# Comms.net
KiCad netlist of a schematic drawn in Altium Designer
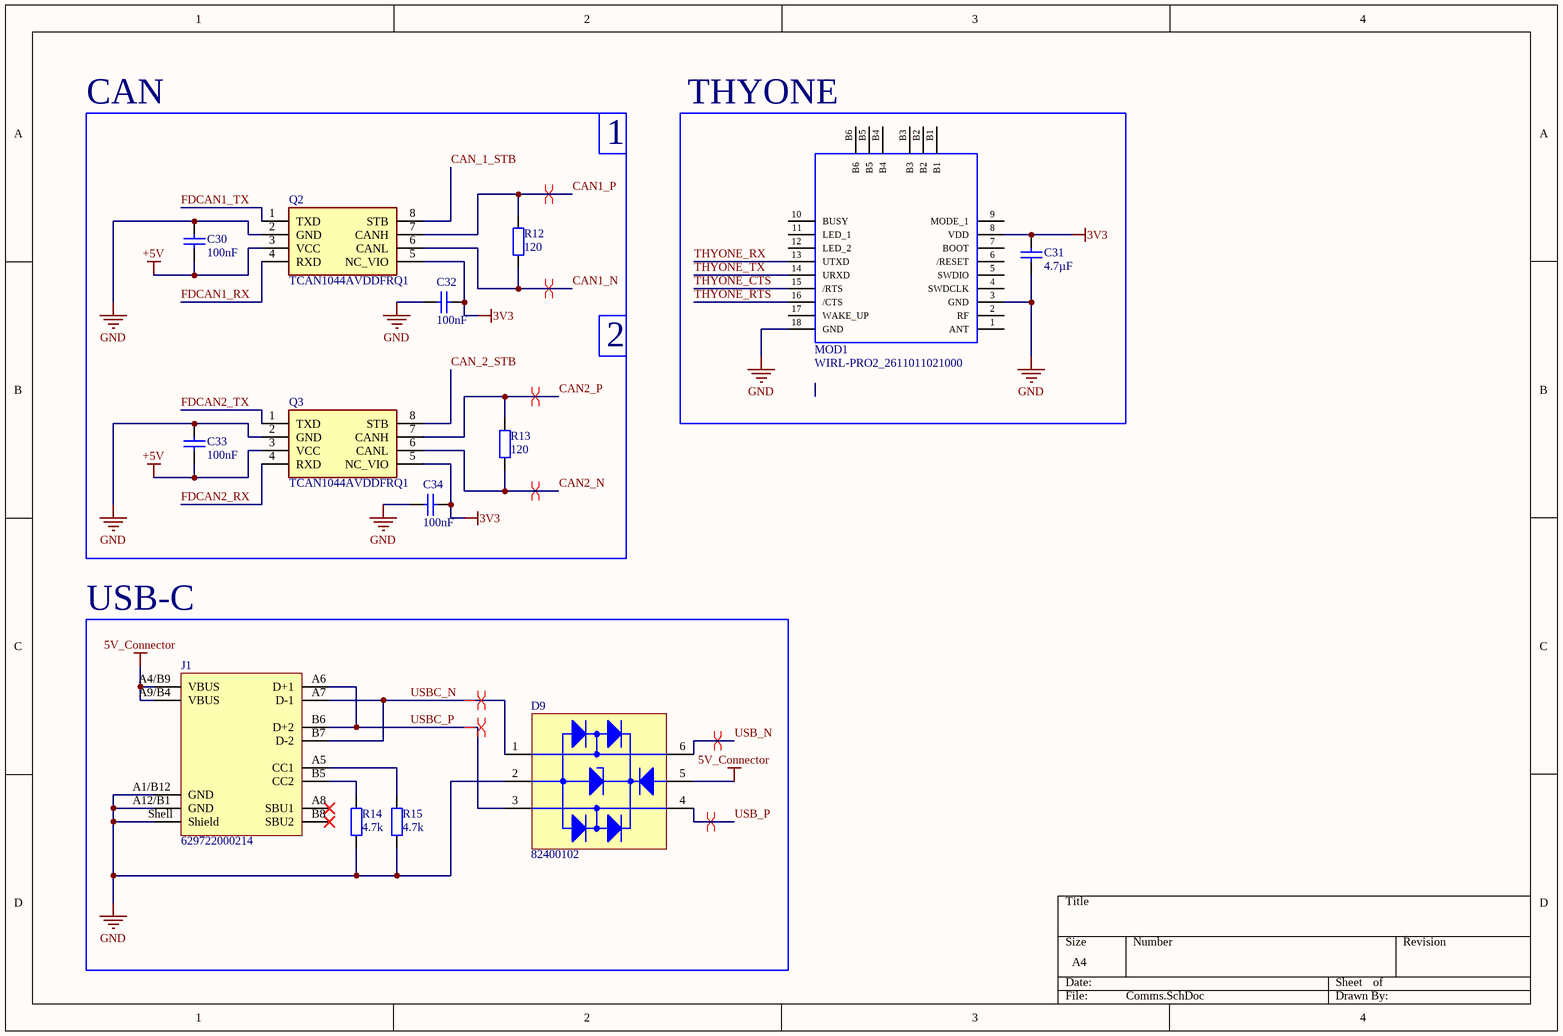
[diagram p0: Comms.SchDoc]

(export (version "E")
  (design (tool "Eeschema 10.0.6"))
  (components
    (comp (ref "C30")
      (value "100nF")
      (footprint "WCAP-CSGP_0603_L1.6W0.8H0.8_Reflow")
      (description "WCAP-CSGP Multilayer Ceramic Chip Capacitor, General Purpose, size 0603, X7R, 100nF, 25VDC")
      (fields
        (field (name "MANUFACTURER") "Wurth Elektronik")
        (field (name "MANUFACTURER PART NUMBER") "885012206071")
      )
      (libsource (lib "LEEM UPM") (part "885012209047R"))
    )
    (comp (ref "C31")
      (value "4.7µF")
      (footprint "WCAP-CSGP_0603_L1.6W0.8H0.8_Reflow")
      (description "WCAP-CSGP Multilayer Ceramic Chip Capacitor, General Purpose, size 0603, X5R, 4.7uF, 10VDC")
      (fields
        (field (name "MANUFACTURER PART NUMBER") "885012106012")
        (field (name "MANUFACTURER") "Wurth Elektronik")
      )
      (libsource (lib "LEEM UPM") (part "885012209047R"))
    )
    (comp (ref "C32")
      (value "100nF")
      (footprint "WCAP-CSGP_0603_L1.6W0.8H0.8_Reflow")
      (description "WCAP-CSGP Multilayer Ceramic Chip Capacitor, General Purpose, size 0603, X7R, 100nF, 25VDC")
      (fields
        (field (name "MANUFACTURER") "Wurth Elektronik")
        (field (name "MANUFACTURER PART NUMBER") "885012206071")
      )
      (libsource (lib "LEEM UPM") (part "885012209047R"))
    )
    (comp (ref "C33")
      (value "100nF")
      (footprint "WCAP-CSGP_0603_L1.6W0.8H0.8_Reflow")
      (description "WCAP-CSGP Multilayer Ceramic Chip Capacitor, General Purpose, size 0603, X7R, 100nF, 25VDC")
      (fields
        (field (name "MANUFACTURER") "Wurth Elektronik")
        (field (name "MANUFACTURER PART NUMBER") "885012206071")
      )
      (libsource (lib "LEEM UPM") (part "885012209047R"))
    )
    (comp (ref "C34")
      (value "100nF")
      (footprint "WCAP-CSGP_0603_L1.6W0.8H0.8_Reflow")
      (description "WCAP-CSGP Multilayer Ceramic Chip Capacitor, General Purpose, size 0603, X7R, 100nF, 25VDC")
      (fields
        (field (name "MANUFACTURER") "Wurth Elektronik")
        (field (name "MANUFACTURER PART NUMBER") "885012206071")
      )
      (libsource (lib "LEEM UPM") (part "885012209047R"))
    )
    (comp (ref "D9")
      (value "82400102")
      (footprint "WE-TVS_SOT23-6L")
      (description "WE-TVS TVS Diode – High Speed Series, SOT23-6L, 2+1 Channel, 5V, 2pF")
      (fields (field (name "MANUFACTURER") "Wurth Elektronik"))
      (libsource (lib "LEEM UPM") (part "82400152"))
    )
    (comp (ref "J1")
      (value "629722000214")
      (footprint "629722000214")
      (description "WR-COM USB 2.0 Type C Receptacle Horizontal SMT")
      (fields (field (name "MANUFACTURER") "Wurth Elektronik"))
      (libsource (lib "LEEM UPM") (part "629722000214"))
    )
    (comp (ref "MOD1")
      (value "WIRL-PRO2_2611011021000")
      (footprint "WE-FP-4+")
      (description "Thyone-I - Radio Modules 2.4 GHz")
      (fields (field (name "PART NUMBER") "2611011021000") (field (name "PUBLISHER") "Wurth Elektronik"))
      (libsource (lib "LEEM UPM") (part "WIRL-PRO2_2611011021000"))
    )
    (comp (ref "Q2")
      (value "TCAN1044AVDDFRQ1")
      (footprint "FP-DDF0008A-MFG")
      (description "Enhanced automotive CAN transceiver with standby 8-SOT-23-THIN -40 to 150")
      (libsource (lib "LEEM UPM") (part "TCAN1044A"))
    )
    (comp (ref "Q3")
      (value "TCAN1044AVDDFRQ1")
      (footprint "FP-DDF0008A-MFG")
      (description "Enhanced automotive CAN transceiver with standby 8-SOT-23-THIN -40 to 150")
      (libsource (lib "LEEM UPM") (part "TCAN1044A"))
    )
    (comp (ref "R12")
      (value "120")
      (footprint "RCS0805120RFKEA-Footprint-1")
      (fields (field (name "POWER") "500mW") (field (name "Comment") "RCS0805120RFKEA"))
      (libsource (lib "LEEM UPM") (part "RCS0805120"))
    )
    (comp (ref "R13")
      (value "120")
      (footprint "RCS0805120RFKEA-Footprint-1")
      (fields (field (name "POWER") "500mW") (field (name "Comment") "RCS0805120RFKEA"))
      (libsource (lib "LEEM UPM") (part "RCS0805120"))
    )
    (comp (ref "R14")
      (value "4.7k")
      (footprint "WRIS-RSKS_0603_Reflow")
      (description "WRIS-RSKS Thick Film Resistor, size 0603, 4700Ohm, 100mW")
      (fields
        (field (name "MANUFACTURER PART NUMBER") "560112116006")
        (field (name "MANUFACTURER") "Wurth Elektronik")
      )
      (libsource (lib "LEEM UPM") (part "560112140010"))
    )
    (comp (ref "R15")
      (value "4.7k")
      (footprint "WRIS-RSKS_0603_Reflow")
      (description "WRIS-RSKS Thick Film Resistor, size 0603, 4700Ohm, 100mW")
      (fields
        (field (name "MANUFACTURER PART NUMBER") "560112116006")
        (field (name "MANUFACTURER") "Wurth Elektronik")
      )
      (libsource (lib "LEEM UPM") (part "560112140010"))
    )
  )
  (nets
    (net (code "1") (name "+5V") (class "Default")
      (node (ref "C30") (pin "1") (pinfunction "1_1") (pintype "passive"))
      (node (ref "C33") (pin "1") (pinfunction "1_1") (pintype "passive"))
      (node (ref "Q2") (pin "3") (pinfunction "VCC_3") (pintype "passive"))
      (node (ref "Q3") (pin "3") (pinfunction "VCC_3") (pintype "passive"))
    )
    (net (code "2") (name "/CAN1_N") (class "Default")
      (node (ref "Q2") (pin "6") (pinfunction "CANL_6") (pintype "passive"))
      (node (ref "R12") (pin "1") (pinfunction "1_1") (pintype "passive"))
    )
    (net (code "3") (name "/CAN1_P") (class "Default")
      (node (ref "Q2") (pin "7") (pinfunction "CANH_7") (pintype "passive"))
      (node (ref "R12") (pin "2") (pinfunction "2_2") (pintype "passive"))
    )
    (net (code "4") (name "/CAN2_N") (class "Default")
      (node (ref "Q3") (pin "6") (pinfunction "CANL_6") (pintype "passive"))
      (node (ref "R13") (pin "1") (pinfunction "1_1") (pintype "passive"))
    )
    (net (code "5") (name "/CAN2_P") (class "Default")
      (node (ref "Q3") (pin "7") (pinfunction "CANH_7") (pintype "passive"))
      (node (ref "R13") (pin "2") (pinfunction "2_2") (pintype "passive"))
    )
    (net (code "6") (name "/CAN_1_STB") (class "Default")
      (node (ref "Q2") (pin "8") (pinfunction "STB_8") (pintype "passive"))
    )
    (net (code "7") (name "/CAN_2_STB") (class "Default")
      (node (ref "Q3") (pin "8") (pinfunction "STB_8") (pintype "passive"))
    )
    (net (code "8") (name "/FDCAN1_RX") (class "Default")
      (node (ref "Q2") (pin "4") (pinfunction "RXD_4") (pintype "passive"))
    )
    (net (code "9") (name "/FDCAN1_TX") (class "Default")
      (node (ref "Q2") (pin "1") (pinfunction "TXD_1") (pintype "passive"))
    )
    (net (code "10") (name "/FDCAN2_RX") (class "Default")
      (node (ref "Q3") (pin "4") (pinfunction "RXD_4") (pintype "passive"))
    )
    (net (code "11") (name "/FDCAN2_TX") (class "Default")
      (node (ref "Q3") (pin "1") (pinfunction "TXD_1") (pintype "passive"))
    )
    (net (code "12") (name "/THYONE_CTS") (class "Default")
      (node (ref "MOD1") (pin "15") (pinfunction "/RTS_15") (pintype "passive"))
    )
    (net (code "13") (name "/THYONE_RTS") (class "Default")
      (node (ref "MOD1") (pin "16") (pinfunction "/CTS_16") (pintype "passive"))
    )
    (net (code "14") (name "/THYONE_RX") (class "Default")
      (node (ref "MOD1") (pin "13") (pinfunction "UTXD_13") (pintype "passive"))
    )
    (net (code "15") (name "/THYONE_TX") (class "Default")
      (node (ref "MOD1") (pin "14") (pinfunction "URXD_14") (pintype "passive"))
    )
    (net (code "16") (name "/USBC_N") (class "Default")
      (node (ref "D9") (pin "1") (pinfunction "I/O_1_1") (pintype "passive"))
      (node (ref "J1") (pin "A7") (pinfunction "D-1_A7") (pintype "passive"))
      (node (ref "J1") (pin "B7") (pinfunction "D-2_B7") (pintype "passive"))
    )
    (net (code "17") (name "/USBC_P") (class "Default")
      (node (ref "D9") (pin "3") (pinfunction "I/O_2_3") (pintype "passive"))
      (node (ref "J1") (pin "A6") (pinfunction "D+1_A6") (pintype "passive"))
      (node (ref "J1") (pin "B6") (pinfunction "D+2_B6") (pintype "passive"))
    )
    (net (code "18") (name "/USB_N") (class "Default")
      (node (ref "D9") (pin "6") (pinfunction "I/O_1_6") (pintype "passive"))
    )
    (net (code "19") (name "/USB_P") (class "Default")
      (node (ref "D9") (pin "4") (pinfunction "I/O_2_4") (pintype "passive"))
    )
    (net (code "20") (name "3V3") (class "Default")
      (node (ref "C31") (pin "1") (pinfunction "1_1") (pintype "passive"))
      (node (ref "C32") (pin "1") (pinfunction "1_1") (pintype "passive"))
      (node (ref "C34") (pin "1") (pinfunction "1_1") (pintype "passive"))
      (node (ref "MOD1") (pin "8") (pinfunction "VDD_8") (pintype "passive"))
      (node (ref "Q2") (pin "5") (pinfunction "NC_VIO_5") (pintype "passive"))
      (node (ref "Q3") (pin "5") (pinfunction "NC_VIO_5") (pintype "passive"))
    )
    (net (code "21") (name "5V_Connector") (class "Default")
      (node (ref "D9") (pin "5") (pinfunction "VDD_5") (pintype "passive"))
      (node (ref "J1") (pin "A4/B9") (pinfunction "VBUS_A4/B9") (pintype "passive"))
      (node (ref "J1") (pin "A9/B4") (pinfunction "VBUS_A9/B4") (pintype "passive"))
    )
    (net (code "22") (name "GND") (class "Default")
      (node (ref "C30") (pin "2") (pinfunction "2_2") (pintype "passive"))
      (node (ref "C31") (pin "2") (pinfunction "2_2") (pintype "passive"))
      (node (ref "C32") (pin "2") (pinfunction "2_2") (pintype "passive"))
      (node (ref "C33") (pin "2") (pinfunction "2_2") (pintype "passive"))
      (node (ref "C34") (pin "2") (pinfunction "2_2") (pintype "passive"))
      (node (ref "D9") (pin "2") (pinfunction "GND_2") (pintype "passive"))
      (node (ref "J1") (pin "A1/B12") (pinfunction "GND_A1/B12") (pintype "passive"))
      (node (ref "J1") (pin "A12/B1") (pinfunction "GND_A12/B1") (pintype "passive"))
      (node (ref "J1") (pin "Shell") (pinfunction "Shield_Shell") (pintype "passive"))
      (node (ref "MOD1") (pin "18") (pinfunction "GND_18") (pintype "passive"))
      (node (ref "MOD1") (pin "3") (pinfunction "GND_3") (pintype "passive"))
      (node (ref "Q2") (pin "2") (pinfunction "GND_2") (pintype "passive"))
      (node (ref "Q3") (pin "2") (pinfunction "GND_2") (pintype "passive"))
      (node (ref "R14") (pin "2") (pinfunction "2_2") (pintype "passive"))
      (node (ref "R15") (pin "2") (pinfunction "2_2") (pintype "passive"))
    )
    (net (code "23") (name "Net-(J1-CC1)") (class "Default")
      (node (ref "J1") (pin "A5") (pinfunction "CC1_A5") (pintype "passive"))
      (node (ref "R15") (pin "1") (pinfunction "1_1") (pintype "passive"))
    )
    (net (code "24") (name "Net-(J1-CC2)") (class "Default")
      (node (ref "J1") (pin "B5") (pinfunction "CC2_B5") (pintype "passive"))
      (node (ref "R14") (pin "1") (pinfunction "1_1") (pintype "passive"))
    )
    (net (code "25") (name "unconnected-(J1-SBU1-PadA8)") (class "Default")
      (node (ref "J1") (pin "A8") (pinfunction "SBU1_A8") (pintype "passive+no_connect"))
    )
    (net (code "26") (name "unconnected-(J1-SBU2-PadB8)") (class "Default")
      (node (ref "J1") (pin "B8") (pinfunction "SBU2_B8") (pintype "passive+no_connect"))
    )
    (net (code "27") (name "unconnected-(MOD1-ANT-Pad1)") (class "Default")
      (node (ref "MOD1") (pin "1") (pinfunction "ANT_1") (pintype "passive"))
    )
    (net (code "28") (name "unconnected-(MOD1-BOOT-Pad7)") (class "Default")
      (node (ref "MOD1") (pin "7") (pinfunction "BOOT_7") (pintype "passive"))
    )
    (net (code "29") (name "unconnected-(MOD1-BUSY-Pad10)") (class "Default")
      (node (ref "MOD1") (pin "10") (pinfunction "BUSY_10") (pintype "passive"))
    )
    (net (code "30") (name "unconnected-(MOD1-LED_1-Pad11)") (class "Default")
      (node (ref "MOD1") (pin "11") (pinfunction "LED_1_11") (pintype "passive"))
    )
    (net (code "31") (name "unconnected-(MOD1-LED_2-Pad12)") (class "Default")
      (node (ref "MOD1") (pin "12") (pinfunction "LED_2_12") (pintype "passive"))
    )
    (net (code "32") (name "unconnected-(MOD1-MODE_1-Pad9)") (class "Default")
      (node (ref "MOD1") (pin "9") (pinfunction "MODE_1_9") (pintype "passive"))
    )
    (net (code "33") (name "unconnected-(MOD1-PadB1)") (class "Default")
      (node (ref "MOD1") (pin "B1") (pinfunction "B1_B1") (pintype "passive"))
    )
    (net (code "34") (name "unconnected-(MOD1-PadB2)") (class "Default")
      (node (ref "MOD1") (pin "B2") (pinfunction "B2_B2") (pintype "passive"))
    )
    (net (code "35") (name "unconnected-(MOD1-PadB3)") (class "Default")
      (node (ref "MOD1") (pin "B3") (pinfunction "B3_B3") (pintype "passive"))
    )
    (net (code "36") (name "unconnected-(MOD1-PadB4)") (class "Default")
      (node (ref "MOD1") (pin "B4") (pinfunction "B4_B4") (pintype "passive"))
    )
    (net (code "37") (name "unconnected-(MOD1-PadB5)") (class "Default")
      (node (ref "MOD1") (pin "B5") (pinfunction "B5_B5") (pintype "passive"))
    )
    (net (code "38") (name "unconnected-(MOD1-PadB6)") (class "Default")
      (node (ref "MOD1") (pin "B6") (pinfunction "B6_B6") (pintype "passive"))
    )
    (net (code "39") (name "unconnected-(MOD1-RF-Pad2)") (class "Default")
      (node (ref "MOD1") (pin "2") (pinfunction "RF_2") (pintype "passive"))
    )
    (net (code "40") (name "unconnected-(MOD1-SWDCLK-Pad4)") (class "Default")
      (node (ref "MOD1") (pin "4") (pinfunction "SWDCLK_4") (pintype "passive"))
    )
    (net (code "41") (name "unconnected-(MOD1-SWDIO-Pad5)") (class "Default")
      (node (ref "MOD1") (pin "5") (pinfunction "SWDIO_5") (pintype "passive"))
    )
    (net (code "42") (name "unconnected-(MOD1-WAKE_UP-Pad17)") (class "Default")
      (node (ref "MOD1") (pin "17") (pinfunction "WAKE_UP_17") (pintype "passive"))
    )
    (net (code "43") (name "unconnected-(MOD1-{slash}RESET-Pad6)") (class "Default")
      (node (ref "MOD1") (pin "6") (pinfunction "/RESET_6") (pintype "passive"))
    )
  )
)
